# LTC4040_to_Breadboard.net
KiCad netlist of a schematic drawn in EAGLE
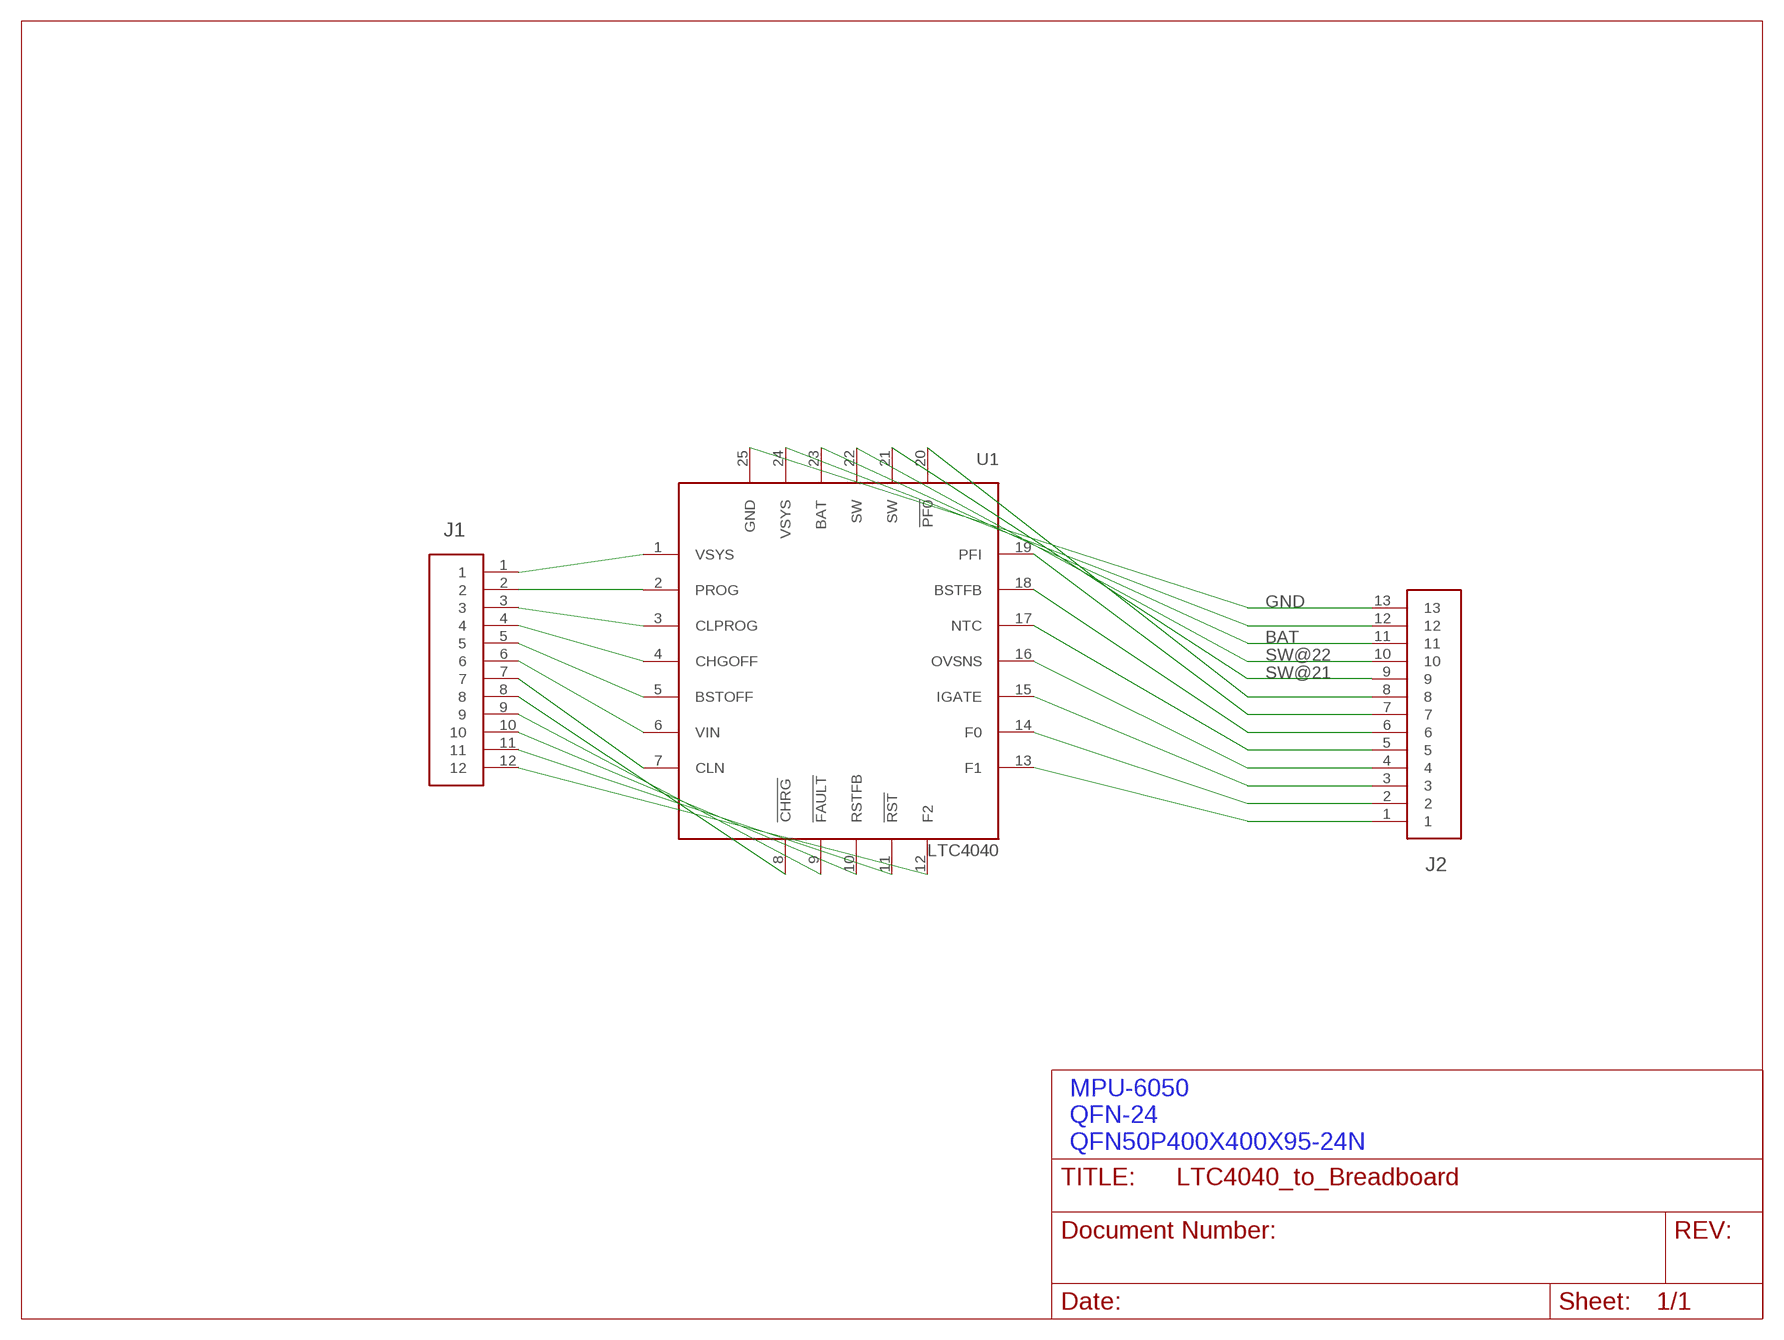
[diagram p0: schematic, sheet 1]

(export (version "E")
  (design (tool "Eeschema 10.0.6"))
  (components
    (comp (ref "J1")
      (value "CONNECTOR_12")
      (footprint "eagle-import:68000-112HLF")
      (libsource (lib "eagle-import") (part "CONNECTOR_12"))
    )
    (comp (ref "J2")
      (value "CONNECTOR_13")
      (footprint "eagle-import:68000-113HLF_NO_SQUARE")
      (libsource (lib "eagle-import") (part "CONNECTOR_13"))
    )
    (comp (ref "U1")
      (value "LTC4040")
      (footprint "eagle-import:QFN50P500X400X80-25N")
      (libsource (lib "eagle-import") (part "LTC4040"))
    )
  )
  (nets
    (net (code "1") (name "/BAT") (class "Default")
      (node (ref "J2") (pin "11") (pinfunction "11_11") (pintype "bidirectional"))
      (node (ref "U1") (pin "23") (pinfunction "BAT_23") (pintype "bidirectional"))
    )
    (net (code "2") (name "/GND") (class "Default")
      (node (ref "J2") (pin "13") (pinfunction "13_13") (pintype "bidirectional"))
      (node (ref "U1") (pin "25") (pinfunction "GND_25") (pintype "bidirectional"))
    )
    (net (code "3") (name "/SW@21") (class "Default")
      (node (ref "J2") (pin "9") (pinfunction "9_9") (pintype "bidirectional"))
      (node (ref "U1") (pin "21") (pinfunction "SW_21") (pintype "bidirectional"))
    )
    (net (code "4") (name "/SW@22") (class "Default")
      (node (ref "J2") (pin "10") (pinfunction "10_10") (pintype "bidirectional"))
      (node (ref "U1") (pin "22") (pinfunction "SW_22") (pintype "bidirectional"))
    )
    (net (code "5") (name "Net-(J1-Pad1)") (class "Default")
      (node (ref "J1") (pin "1") (pinfunction "1_1") (pintype "bidirectional"))
      (node (ref "U1") (pin "1") (pinfunction "VSYS_1") (pintype "bidirectional"))
    )
    (net (code "6") (name "Net-(J2-Pad12)") (class "Default")
      (node (ref "J2") (pin "12") (pinfunction "12_12") (pintype "bidirectional"))
      (node (ref "U1") (pin "24") (pinfunction "VSYS_24") (pintype "bidirectional"))
    )
    (net (code "7") (name "Net-(U1-BSTFB)") (class "Default")
      (node (ref "J2") (pin "6") (pinfunction "6_6") (pintype "bidirectional"))
      (node (ref "U1") (pin "18") (pinfunction "BSTFB_18") (pintype "bidirectional"))
    )
    (net (code "8") (name "Net-(U1-BSTOFF)") (class "Default")
      (node (ref "J1") (pin "5") (pinfunction "5_5") (pintype "bidirectional"))
      (node (ref "U1") (pin "5") (pinfunction "BSTOFF_5") (pintype "bidirectional"))
    )
    (net (code "9") (name "Net-(U1-CHGOFF)") (class "Default")
      (node (ref "J1") (pin "4") (pinfunction "4_4") (pintype "bidirectional"))
      (node (ref "U1") (pin "4") (pinfunction "CHGOFF_4") (pintype "bidirectional"))
    )
    (net (code "10") (name "Net-(U1-CLN)") (class "Default")
      (node (ref "J1") (pin "7") (pinfunction "7_7") (pintype "bidirectional"))
      (node (ref "U1") (pin "7") (pinfunction "CLN_7") (pintype "bidirectional"))
    )
    (net (code "11") (name "Net-(U1-CLPROG)") (class "Default")
      (node (ref "J1") (pin "3") (pinfunction "3_3") (pintype "bidirectional"))
      (node (ref "U1") (pin "3") (pinfunction "CLPROG_3") (pintype "bidirectional"))
    )
    (net (code "12") (name "Net-(U1-F0)") (class "Default")
      (node (ref "J2") (pin "2") (pinfunction "2_2") (pintype "bidirectional"))
      (node (ref "U1") (pin "14") (pinfunction "F0_14") (pintype "bidirectional"))
    )
    (net (code "13") (name "Net-(U1-F1)") (class "Default")
      (node (ref "J2") (pin "1") (pinfunction "1_1") (pintype "bidirectional"))
      (node (ref "U1") (pin "13") (pinfunction "F1_13") (pintype "bidirectional"))
    )
    (net (code "14") (name "Net-(U1-F2)") (class "Default")
      (node (ref "J1") (pin "12") (pinfunction "12_12") (pintype "bidirectional"))
      (node (ref "U1") (pin "12") (pinfunction "F2_12") (pintype "bidirectional"))
    )
    (net (code "15") (name "Net-(U1-IGATE)") (class "Default")
      (node (ref "J2") (pin "3") (pinfunction "3_3") (pintype "bidirectional"))
      (node (ref "U1") (pin "15") (pinfunction "IGATE_15") (pintype "bidirectional"))
    )
    (net (code "16") (name "Net-(U1-NTC)") (class "Default")
      (node (ref "J2") (pin "5") (pinfunction "5_5") (pintype "bidirectional"))
      (node (ref "U1") (pin "17") (pinfunction "NTC_17") (pintype "bidirectional"))
    )
    (net (code "17") (name "Net-(U1-OVSNS)") (class "Default")
      (node (ref "J2") (pin "4") (pinfunction "4_4") (pintype "bidirectional"))
      (node (ref "U1") (pin "16") (pinfunction "OVSNS_16") (pintype "bidirectional"))
    )
    (net (code "18") (name "Net-(U1-PFI)") (class "Default")
      (node (ref "J2") (pin "7") (pinfunction "7_7") (pintype "bidirectional"))
      (node (ref "U1") (pin "19") (pinfunction "PFI_19") (pintype "bidirectional"))
    )
    (net (code "19") (name "Net-(U1-PROG)") (class "Default")
      (node (ref "J1") (pin "2") (pinfunction "2_2") (pintype "bidirectional"))
      (node (ref "U1") (pin "2") (pinfunction "PROG_2") (pintype "bidirectional"))
    )
    (net (code "20") (name "Net-(U1-RSTFB)") (class "Default")
      (node (ref "J1") (pin "10") (pinfunction "10_10") (pintype "bidirectional"))
      (node (ref "U1") (pin "10") (pinfunction "RSTFB_10") (pintype "bidirectional"))
    )
    (net (code "21") (name "Net-(U1-VIN)") (class "Default")
      (node (ref "J1") (pin "6") (pinfunction "6_6") (pintype "bidirectional"))
      (node (ref "U1") (pin "6") (pinfunction "VIN_6") (pintype "bidirectional"))
    )
    (net (code "22") (name "Net-(U1-~{CHRG})") (class "Default")
      (node (ref "J1") (pin "8") (pinfunction "8_8") (pintype "bidirectional"))
      (node (ref "U1") (pin "8") (pinfunction "~{CHRG}_8") (pintype "bidirectional"))
    )
    (net (code "23") (name "Net-(U1-~{FAULT})") (class "Default")
      (node (ref "J1") (pin "9") (pinfunction "9_9") (pintype "bidirectional"))
      (node (ref "U1") (pin "9") (pinfunction "~{FAULT}_9") (pintype "bidirectional"))
    )
    (net (code "24") (name "Net-(U1-~{PF0})") (class "Default")
      (node (ref "J2") (pin "8") (pinfunction "8_8") (pintype "bidirectional"))
      (node (ref "U1") (pin "20") (pinfunction "~{PF0}_20") (pintype "bidirectional"))
    )
    (net (code "25") (name "Net-(U1-~{RST})") (class "Default")
      (node (ref "J1") (pin "11") (pinfunction "11_11") (pintype "bidirectional"))
      (node (ref "U1") (pin "11") (pinfunction "~{RST}_11") (pintype "bidirectional"))
    )
  )
)
